# Interface.net
KiCad netlist of a schematic drawn in Altium Designer
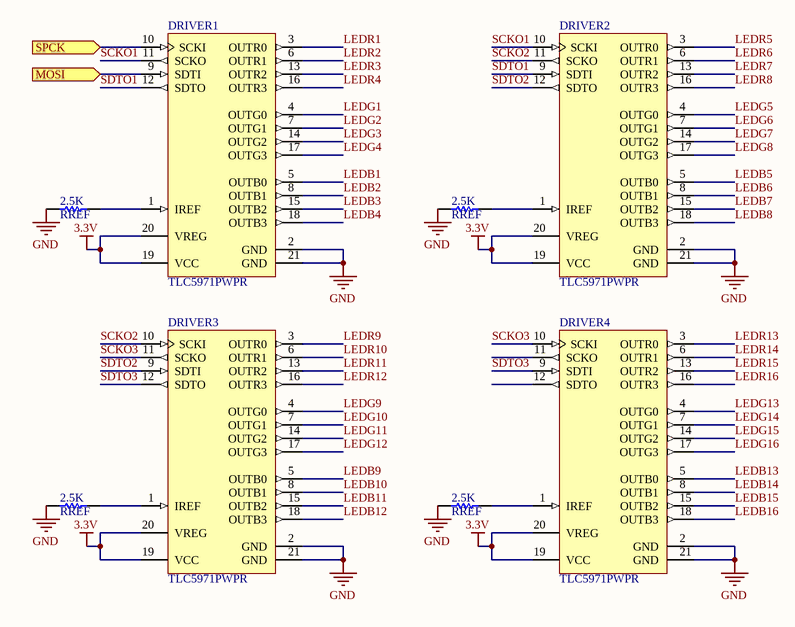
[diagram p0: Interface.SchDoc]

(export (version "E")
  (design (tool "Eeschema 10.0.6"))
  (components
    (comp (ref "DRIVER1")
      (value "TLC5971PWPR")
      (footprint "TI-PWP20-2965X2290TP_N")
      (fields (field (name "MANUFACTURER") "Texas Instruments"))
      (libsource (lib "TI Power Management Lighting and Display") (part "TLC5971PWPR"))
    )
    (comp (ref "DRIVER2")
      (value "TLC5971PWPR")
      (footprint "TI-PWP20-2965X2290TP_N")
      (fields (field (name "MANUFACTURER") "Texas Instruments"))
      (libsource (lib "TI Power Management Lighting and Display") (part "TLC5971PWPR"))
    )
    (comp (ref "DRIVER3")
      (value "TLC5971PWPR")
      (footprint "TI-PWP20-2965X2290TP_N")
      (fields (field (name "MANUFACTURER") "Texas Instruments"))
      (libsource (lib "TI Power Management Lighting and Display") (part "TLC5971PWPR"))
    )
    (comp (ref "DRIVER4")
      (value "TLC5971PWPR")
      (footprint "TI-PWP20-2965X2290TP_N")
      (fields (field (name "MANUFACTURER") "Texas Instruments"))
      (libsource (lib "TI Power Management Lighting and Display") (part "TLC5971PWPR"))
    )
    (comp (ref "R1")
      (value "RREF")
      (footprint "AXIAL-0.3")
      (description "Resistor")
      (fields (field (name "ALTIUM_VALUE") "2.5K") (field (name "PUBLISHER") "Altium Limited"))
      (libsource (lib "Miscellaneous Devices") (part "Res1"))
    )
    (comp (ref "R2")
      (value "RREF")
      (footprint "AXIAL-0.3")
      (description "Resistor")
      (fields (field (name "ALTIUM_VALUE") "2.5K") (field (name "PUBLISHER") "Altium Limited"))
      (libsource (lib "Miscellaneous Devices") (part "Res1"))
    )
    (comp (ref "R3")
      (value "RREF")
      (footprint "AXIAL-0.3")
      (description "Resistor")
      (fields (field (name "ALTIUM_VALUE") "2.5K") (field (name "PUBLISHER") "Altium Limited"))
      (libsource (lib "Miscellaneous Devices") (part "Res1"))
    )
    (comp (ref "R4")
      (value "RREF")
      (footprint "AXIAL-0.3")
      (description "Resistor")
      (fields (field (name "ALTIUM_VALUE") "2.5K") (field (name "PUBLISHER") "Altium Limited"))
      (libsource (lib "Miscellaneous Devices") (part "Res1"))
    )
  )
  (nets
    (net (code "1") (name "/LEDB1") (class "Default")
      (node (ref "DRIVER1") (pin "5") (pinfunction "OUTB0_5") (pintype "output"))
    )
    (net (code "2") (name "/LEDB2") (class "Default")
      (node (ref "DRIVER1") (pin "8") (pinfunction "OUTB1_8") (pintype "output"))
    )
    (net (code "3") (name "/LEDB3") (class "Default")
      (node (ref "DRIVER1") (pin "15") (pinfunction "OUTB2_15") (pintype "output"))
    )
    (net (code "4") (name "/LEDB4") (class "Default")
      (node (ref "DRIVER1") (pin "18") (pinfunction "OUTB3_18") (pintype "output"))
    )
    (net (code "5") (name "/LEDB5") (class "Default")
      (node (ref "DRIVER2") (pin "5") (pinfunction "OUTB0_5") (pintype "output"))
    )
    (net (code "6") (name "/LEDB6") (class "Default")
      (node (ref "DRIVER2") (pin "8") (pinfunction "OUTB1_8") (pintype "output"))
    )
    (net (code "7") (name "/LEDB7") (class "Default")
      (node (ref "DRIVER2") (pin "15") (pinfunction "OUTB2_15") (pintype "output"))
    )
    (net (code "8") (name "/LEDB8") (class "Default")
      (node (ref "DRIVER2") (pin "18") (pinfunction "OUTB3_18") (pintype "output"))
    )
    (net (code "9") (name "/LEDB9") (class "Default")
      (node (ref "DRIVER3") (pin "5") (pinfunction "OUTB0_5") (pintype "output"))
    )
    (net (code "10") (name "/LEDB10") (class "Default")
      (node (ref "DRIVER3") (pin "8") (pinfunction "OUTB1_8") (pintype "output"))
    )
    (net (code "11") (name "/LEDB11") (class "Default")
      (node (ref "DRIVER3") (pin "15") (pinfunction "OUTB2_15") (pintype "output"))
    )
    (net (code "12") (name "/LEDB12") (class "Default")
      (node (ref "DRIVER3") (pin "18") (pinfunction "OUTB3_18") (pintype "output"))
    )
    (net (code "13") (name "/LEDB13") (class "Default")
      (node (ref "DRIVER4") (pin "5") (pinfunction "OUTB0_5") (pintype "output"))
    )
    (net (code "14") (name "/LEDB14") (class "Default")
      (node (ref "DRIVER4") (pin "8") (pinfunction "OUTB1_8") (pintype "output"))
    )
    (net (code "15") (name "/LEDB15") (class "Default")
      (node (ref "DRIVER4") (pin "15") (pinfunction "OUTB2_15") (pintype "output"))
    )
    (net (code "16") (name "/LEDB16") (class "Default")
      (node (ref "DRIVER4") (pin "18") (pinfunction "OUTB3_18") (pintype "output"))
    )
    (net (code "17") (name "/LEDG1") (class "Default")
      (node (ref "DRIVER1") (pin "4") (pinfunction "OUTG0_4") (pintype "output"))
    )
    (net (code "18") (name "/LEDG2") (class "Default")
      (node (ref "DRIVER1") (pin "7") (pinfunction "OUTG1_7") (pintype "output"))
    )
    (net (code "19") (name "/LEDG3") (class "Default")
      (node (ref "DRIVER1") (pin "14") (pinfunction "OUTG2_14") (pintype "output"))
    )
    (net (code "20") (name "/LEDG4") (class "Default")
      (node (ref "DRIVER1") (pin "17") (pinfunction "OUTG3_17") (pintype "output"))
    )
    (net (code "21") (name "/LEDG5") (class "Default")
      (node (ref "DRIVER2") (pin "4") (pinfunction "OUTG0_4") (pintype "output"))
    )
    (net (code "22") (name "/LEDG6") (class "Default")
      (node (ref "DRIVER2") (pin "7") (pinfunction "OUTG1_7") (pintype "output"))
    )
    (net (code "23") (name "/LEDG7") (class "Default")
      (node (ref "DRIVER2") (pin "14") (pinfunction "OUTG2_14") (pintype "output"))
    )
    (net (code "24") (name "/LEDG8") (class "Default")
      (node (ref "DRIVER2") (pin "17") (pinfunction "OUTG3_17") (pintype "output"))
    )
    (net (code "25") (name "/LEDG9") (class "Default")
      (node (ref "DRIVER3") (pin "4") (pinfunction "OUTG0_4") (pintype "output"))
    )
    (net (code "26") (name "/LEDG10") (class "Default")
      (node (ref "DRIVER3") (pin "7") (pinfunction "OUTG1_7") (pintype "output"))
    )
    (net (code "27") (name "/LEDG11") (class "Default")
      (node (ref "DRIVER3") (pin "14") (pinfunction "OUTG2_14") (pintype "output"))
    )
    (net (code "28") (name "/LEDG12") (class "Default")
      (node (ref "DRIVER3") (pin "17") (pinfunction "OUTG3_17") (pintype "output"))
    )
    (net (code "29") (name "/LEDG13") (class "Default")
      (node (ref "DRIVER4") (pin "4") (pinfunction "OUTG0_4") (pintype "output"))
    )
    (net (code "30") (name "/LEDG14") (class "Default")
      (node (ref "DRIVER4") (pin "7") (pinfunction "OUTG1_7") (pintype "output"))
    )
    (net (code "31") (name "/LEDG15") (class "Default")
      (node (ref "DRIVER4") (pin "14") (pinfunction "OUTG2_14") (pintype "output"))
    )
    (net (code "32") (name "/LEDG16") (class "Default")
      (node (ref "DRIVER4") (pin "17") (pinfunction "OUTG3_17") (pintype "output"))
    )
    (net (code "33") (name "/LEDR1") (class "Default")
      (node (ref "DRIVER1") (pin "3") (pinfunction "OUTR0_3") (pintype "output"))
    )
    (net (code "34") (name "/LEDR2") (class "Default")
      (node (ref "DRIVER1") (pin "6") (pinfunction "OUTR1_6") (pintype "output"))
    )
    (net (code "35") (name "/LEDR3") (class "Default")
      (node (ref "DRIVER1") (pin "13") (pinfunction "OUTR2_13") (pintype "output"))
    )
    (net (code "36") (name "/LEDR4") (class "Default")
      (node (ref "DRIVER1") (pin "16") (pinfunction "OUTR3_16") (pintype "output"))
    )
    (net (code "37") (name "/LEDR5") (class "Default")
      (node (ref "DRIVER2") (pin "3") (pinfunction "OUTR0_3") (pintype "output"))
    )
    (net (code "38") (name "/LEDR6") (class "Default")
      (node (ref "DRIVER2") (pin "6") (pinfunction "OUTR1_6") (pintype "output"))
    )
    (net (code "39") (name "/LEDR7") (class "Default")
      (node (ref "DRIVER2") (pin "13") (pinfunction "OUTR2_13") (pintype "output"))
    )
    (net (code "40") (name "/LEDR8") (class "Default")
      (node (ref "DRIVER2") (pin "16") (pinfunction "OUTR3_16") (pintype "output"))
    )
    (net (code "41") (name "/LEDR9") (class "Default")
      (node (ref "DRIVER3") (pin "3") (pinfunction "OUTR0_3") (pintype "output"))
    )
    (net (code "42") (name "/LEDR10") (class "Default")
      (node (ref "DRIVER3") (pin "6") (pinfunction "OUTR1_6") (pintype "output"))
    )
    (net (code "43") (name "/LEDR11") (class "Default")
      (node (ref "DRIVER3") (pin "13") (pinfunction "OUTR2_13") (pintype "output"))
    )
    (net (code "44") (name "/LEDR12") (class "Default")
      (node (ref "DRIVER3") (pin "16") (pinfunction "OUTR3_16") (pintype "output"))
    )
    (net (code "45") (name "/LEDR13") (class "Default")
      (node (ref "DRIVER4") (pin "3") (pinfunction "OUTR0_3") (pintype "output"))
    )
    (net (code "46") (name "/LEDR14") (class "Default")
      (node (ref "DRIVER4") (pin "6") (pinfunction "OUTR1_6") (pintype "output"))
    )
    (net (code "47") (name "/LEDR15") (class "Default")
      (node (ref "DRIVER4") (pin "13") (pinfunction "OUTR2_13") (pintype "output"))
    )
    (net (code "48") (name "/LEDR16") (class "Default")
      (node (ref "DRIVER4") (pin "16") (pinfunction "OUTR3_16") (pintype "output"))
    )
    (net (code "49") (name "/MOSI") (class "Default")
      (node (ref "DRIVER1") (pin "9") (pinfunction "SDTI_9") (pintype "input"))
    )
    (net (code "50") (name "/SCKO1") (class "Default")
      (node (ref "DRIVER1") (pin "11") (pinfunction "SCKO_11") (pintype "output"))
      (node (ref "DRIVER2") (pin "10") (pinfunction "SCKI_10") (pintype "input"))
    )
    (net (code "51") (name "/SCKO2") (class "Default")
      (node (ref "DRIVER2") (pin "11") (pinfunction "SCKO_11") (pintype "output"))
      (node (ref "DRIVER3") (pin "10") (pinfunction "SCKI_10") (pintype "input"))
    )
    (net (code "52") (name "/SCKO3") (class "Default")
      (node (ref "DRIVER3") (pin "11") (pinfunction "SCKO_11") (pintype "output"))
      (node (ref "DRIVER4") (pin "10") (pinfunction "SCKI_10") (pintype "input"))
    )
    (net (code "53") (name "/SDTO1") (class "Default")
      (node (ref "DRIVER1") (pin "12") (pinfunction "SDTO_12") (pintype "output"))
      (node (ref "DRIVER2") (pin "9") (pinfunction "SDTI_9") (pintype "input"))
    )
    (net (code "54") (name "/SDTO2") (class "Default")
      (node (ref "DRIVER2") (pin "12") (pinfunction "SDTO_12") (pintype "output"))
      (node (ref "DRIVER3") (pin "9") (pinfunction "SDTI_9") (pintype "input"))
    )
    (net (code "55") (name "/SDTO3") (class "Default")
      (node (ref "DRIVER3") (pin "12") (pinfunction "SDTO_12") (pintype "output"))
      (node (ref "DRIVER4") (pin "9") (pinfunction "SDTI_9") (pintype "input"))
    )
    (net (code "56") (name "/SPCK") (class "Default")
      (node (ref "DRIVER1") (pin "10") (pinfunction "SCKI_10") (pintype "input"))
    )
    (net (code "57") (name "3.3V") (class "Default")
      (node (ref "DRIVER1") (pin "19") (pinfunction "VCC_19") (pintype "power_in"))
      (node (ref "DRIVER1") (pin "20") (pinfunction "VREG_20") (pintype "power_in"))
      (node (ref "DRIVER2") (pin "19") (pinfunction "VCC_19") (pintype "power_in"))
      (node (ref "DRIVER2") (pin "20") (pinfunction "VREG_20") (pintype "power_in"))
      (node (ref "DRIVER3") (pin "19") (pinfunction "VCC_19") (pintype "power_in"))
      (node (ref "DRIVER3") (pin "20") (pinfunction "VREG_20") (pintype "power_in"))
      (node (ref "DRIVER4") (pin "19") (pinfunction "VCC_19") (pintype "power_in"))
      (node (ref "DRIVER4") (pin "20") (pinfunction "VREG_20") (pintype "power_in"))
    )
    (net (code "58") (name "GND") (class "Default")
      (node (ref "DRIVER1") (pin "2") (pinfunction "GND_2") (pintype "power_in"))
      (node (ref "DRIVER1") (pin "21") (pinfunction "GND_21") (pintype "power_in"))
      (node (ref "DRIVER2") (pin "2") (pinfunction "GND_2") (pintype "power_in"))
      (node (ref "DRIVER2") (pin "21") (pinfunction "GND_21") (pintype "power_in"))
      (node (ref "DRIVER3") (pin "2") (pinfunction "GND_2") (pintype "power_in"))
      (node (ref "DRIVER3") (pin "21") (pinfunction "GND_21") (pintype "power_in"))
      (node (ref "DRIVER4") (pin "2") (pinfunction "GND_2") (pintype "power_in"))
      (node (ref "DRIVER4") (pin "21") (pinfunction "GND_21") (pintype "power_in"))
      (node (ref "R1") (pin "1") (pinfunction "1_1") (pintype "passive"))
      (node (ref "R2") (pin "1") (pinfunction "1_1") (pintype "passive"))
      (node (ref "R3") (pin "1") (pinfunction "1_1") (pintype "passive"))
      (node (ref "R4") (pin "1") (pinfunction "1_1") (pintype "passive"))
    )
    (net (code "59") (name "Net-(DRIVER1-IREF)") (class "Default")
      (node (ref "DRIVER1") (pin "1") (pinfunction "IREF_1") (pintype "input"))
      (node (ref "R1") (pin "2") (pinfunction "2_2") (pintype "passive"))
    )
    (net (code "60") (name "Net-(DRIVER2-IREF)") (class "Default")
      (node (ref "DRIVER2") (pin "1") (pinfunction "IREF_1") (pintype "input"))
      (node (ref "R2") (pin "2") (pinfunction "2_2") (pintype "passive"))
    )
    (net (code "61") (name "Net-(DRIVER3-IREF)") (class "Default")
      (node (ref "DRIVER3") (pin "1") (pinfunction "IREF_1") (pintype "input"))
      (node (ref "R3") (pin "2") (pinfunction "2_2") (pintype "passive"))
    )
    (net (code "62") (name "Net-(DRIVER4-IREF)") (class "Default")
      (node (ref "DRIVER4") (pin "1") (pinfunction "IREF_1") (pintype "input"))
      (node (ref "R4") (pin "2") (pinfunction "2_2") (pintype "passive"))
    )
    (net (code "63") (name "unconnected-(DRIVER4-SCKO-Pad11)") (class "Default")
      (node (ref "DRIVER4") (pin "11") (pinfunction "SCKO_11") (pintype "output"))
    )
    (net (code "64") (name "unconnected-(DRIVER4-SDTO-Pad12)") (class "Default")
      (node (ref "DRIVER4") (pin "12") (pinfunction "SDTO_12") (pintype "output"))
    )
  )
)
